# 1_Power.net
KiCad netlist of a schematic drawn in Altium Designer
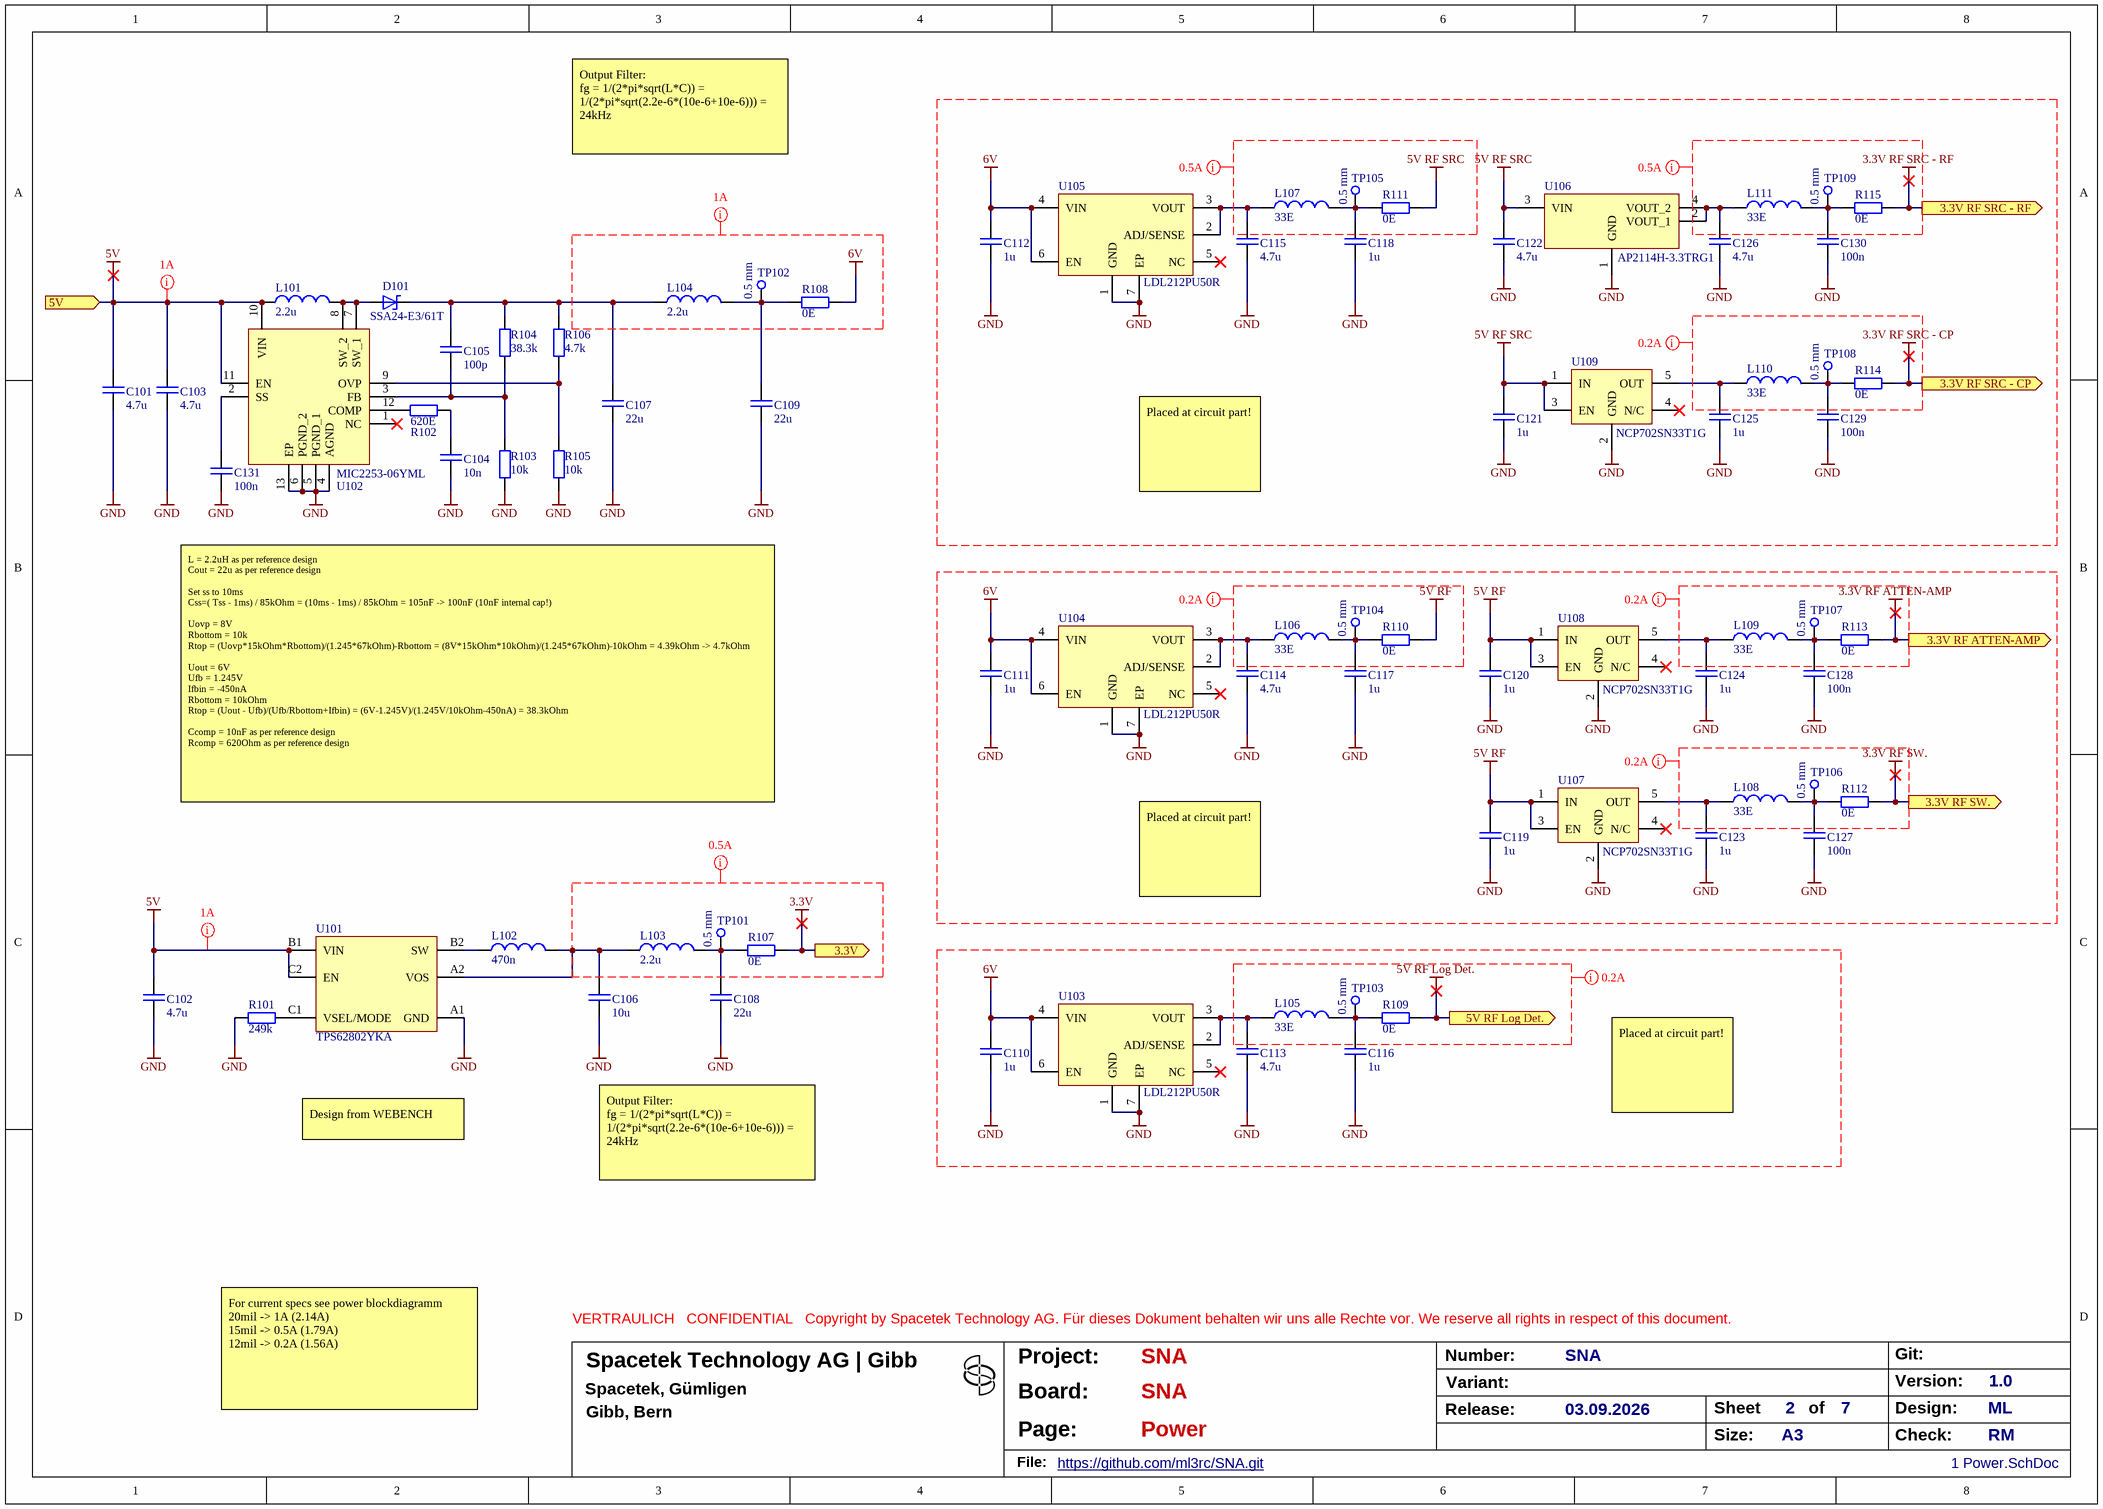
[diagram p0: 1 Power.SchDoc]

(export (version "E")
  (design (tool "Eeschema 10.0.6"))
  (components
    (comp (ref "C101")
      (value "4.7u")
      (footprint "STT--CC--0805")
      (description "Capacitor ceramic 4.7u 25V 10% X7R  SMD--0805")
      (fields (field (name "MANUFACTURER") "Samsung Electro-Mechanics") (field (name "TOLERANCE") "10%"))
      (libsource (lib "Spacetek Technology AG") (part "C--std"))
    )
    (comp (ref "C102")
      (value "4.7u")
      (footprint "STT--CC--0805")
      (description "Capacitor ceramic 4.7u 25V 10% X7R  SMD--0805")
      (fields (field (name "MANUFACTURER") "Samsung Electro-Mechanics") (field (name "TOLERANCE") "10%"))
      (libsource (lib "Spacetek Technology AG") (part "C--std"))
    )
    (comp (ref "C103")
      (value "4.7u")
      (footprint "STT--CC--0805")
      (description "Capacitor ceramic 4.7u 25V 10% X7R  SMD--0805")
      (fields (field (name "MANUFACTURER") "Samsung Electro-Mechanics") (field (name "TOLERANCE") "10%"))
      (libsource (lib "Spacetek Technology AG") (part "C--std"))
    )
    (comp (ref "C104")
      (value "10n")
      (footprint "STT--CC--0603")
      (description "Capacitor ceramic 10n 50V 5% C0G/NPO  SMD--0603")
      (fields (field (name "VOLTAGE") "50V") (field (name "TOLERANCE") "+/-5%"))
      (libsource (lib "Spacetek Technology AG") (part "C--std"))
    )
    (comp (ref "C105")
      (value "100p")
      (footprint "STT--CC--0402")
      (description "Capacitor ceramic 100p 50V 5% C0G AEC-Q200 SMD--0402")
      (fields
        (field (name "PARTNUMBER") "CL05C101JB51PND")
        (field (name "MANUFACTURER") "Samsung Electro-Mechanics")
      )
      (libsource (lib "Spacetek Technology AG") (part "C--std"))
    )
    (comp (ref "C106")
      (value "10u")
      (footprint "STT--CC--0603")
      (description "Capacitor ceramic 10u 25V 20% X5R  SMD--0603")
      (fields (field (name "TOLERANCE") "20%") (field (name "PARTNUMBER") "GRM188R61E106MA73D"))
      (libsource (lib "Spacetek Technology AG") (part "C--std"))
    )
    (comp (ref "C107")
      (value "22u")
      (footprint "STT--CC--0805")
      (description "Capacitor ceramic 22u 25V 20% X5R  SMD--0805")
      (fields (field (name "VOLTAGE") "25V") (field (name "TOLERANCE") "20%"))
      (libsource (lib "Spacetek Technology AG") (part "C--std"))
    )
    (comp (ref "C108")
      (value "22u")
      (footprint "STT--CC--0805")
      (description "Capacitor ceramic 22u 25V 20% X5R  SMD--0805")
      (fields (field (name "VOLTAGE") "25V") (field (name "TOLERANCE") "20%"))
      (libsource (lib "Spacetek Technology AG") (part "C--std"))
    )
    (comp (ref "C109")
      (value "22u")
      (footprint "STT--CC--0805")
      (description "Capacitor ceramic 22u 25V 20% X5R  SMD--0805")
      (fields (field (name "VOLTAGE") "25V") (field (name "TOLERANCE") "20%"))
      (libsource (lib "Spacetek Technology AG") (part "C--std"))
    )
    (comp (ref "C110")
      (value "1u")
      (footprint "STT--CC--0603")
      (description "CAP CER 1UF 35V X7R 0603 10%")
      (fields
        (field (name "MANUFACTURER") "TDK Corporation")
        (field (name "PARTNUMBER") "C1608X7R1V105K080AC")
      )
      (libsource (lib "Spacetek Technology AG") (part "C--std"))
    )
    (comp (ref "C111")
      (value "1u")
      (footprint "STT--CC--0603")
      (description "CAP CER 1UF 35V X7R 0603 10%")
      (fields
        (field (name "MANUFACTURER") "TDK Corporation")
        (field (name "PARTNUMBER") "C1608X7R1V105K080AC")
      )
      (libsource (lib "Spacetek Technology AG") (part "C--std"))
    )
    (comp (ref "C112")
      (value "1u")
      (footprint "STT--CC--0603")
      (description "CAP CER 1UF 35V X7R 0603 10%")
      (fields
        (field (name "MANUFACTURER") "TDK Corporation")
        (field (name "PARTNUMBER") "C1608X7R1V105K080AC")
      )
      (libsource (lib "Spacetek Technology AG") (part "C--std"))
    )
    (comp (ref "C113")
      (value "4.7u")
      (footprint "STT--CC--0805")
      (description "Capacitor ceramic 4.7u 25V 10% X7R  SMD--0805")
      (fields (field (name "MANUFACTURER") "Samsung Electro-Mechanics") (field (name "TOLERANCE") "10%"))
      (libsource (lib "Spacetek Technology AG") (part "C--std"))
    )
    (comp (ref "C114")
      (value "4.7u")
      (footprint "STT--CC--0805")
      (description "Capacitor ceramic 4.7u 25V 10% X7R  SMD--0805")
      (fields (field (name "MANUFACTURER") "Samsung Electro-Mechanics") (field (name "TOLERANCE") "10%"))
      (libsource (lib "Spacetek Technology AG") (part "C--std"))
    )
    (comp (ref "C115")
      (value "4.7u")
      (footprint "STT--CC--0805")
      (description "Capacitor ceramic 4.7u 25V 10% X7R  SMD--0805")
      (fields (field (name "MANUFACTURER") "Samsung Electro-Mechanics") (field (name "TOLERANCE") "10%"))
      (libsource (lib "Spacetek Technology AG") (part "C--std"))
    )
    (comp (ref "C116")
      (value "1u")
      (footprint "STT--CC--0603")
      (description "CAP CER 1UF 35V X7R 0603 10%")
      (fields
        (field (name "MANUFACTURER") "TDK Corporation")
        (field (name "PARTNUMBER") "C1608X7R1V105K080AC")
      )
      (libsource (lib "Spacetek Technology AG") (part "C--std"))
    )
    (comp (ref "C117")
      (value "1u")
      (footprint "STT--CC--0603")
      (description "CAP CER 1UF 35V X7R 0603 10%")
      (fields
        (field (name "MANUFACTURER") "TDK Corporation")
        (field (name "PARTNUMBER") "C1608X7R1V105K080AC")
      )
      (libsource (lib "Spacetek Technology AG") (part "C--std"))
    )
    (comp (ref "C118")
      (value "1u")
      (footprint "STT--CC--0603")
      (description "CAP CER 1UF 35V X7R 0603 10%")
      (fields
        (field (name "MANUFACTURER") "TDK Corporation")
        (field (name "PARTNUMBER") "C1608X7R1V105K080AC")
      )
      (libsource (lib "Spacetek Technology AG") (part "C--std"))
    )
    (comp (ref "C119")
      (value "1u")
      (footprint "STT--CC--0603")
      (description "CAP CER 1UF 35V X7R 0603 10%")
      (fields
        (field (name "MANUFACTURER") "TDK Corporation")
        (field (name "PARTNUMBER") "C1608X7R1V105K080AC")
      )
      (libsource (lib "Spacetek Technology AG") (part "C--std"))
    )
    (comp (ref "C120")
      (value "1u")
      (footprint "STT--CC--0603")
      (description "CAP CER 1UF 35V X7R 0603 10%")
      (fields
        (field (name "MANUFACTURER") "TDK Corporation")
        (field (name "PARTNUMBER") "C1608X7R1V105K080AC")
      )
      (libsource (lib "Spacetek Technology AG") (part "C--std"))
    )
    (comp (ref "C121")
      (value "1u")
      (footprint "STT--CC--0603")
      (description "CAP CER 1UF 35V X7R 0603 10%")
      (fields
        (field (name "MANUFACTURER") "TDK Corporation")
        (field (name "PARTNUMBER") "C1608X7R1V105K080AC")
      )
      (libsource (lib "Spacetek Technology AG") (part "C--std"))
    )
    (comp (ref "C122")
      (value "4.7u")
      (footprint "STT--CC--0805")
      (description "Capacitor ceramic 4.7u 25V 10% X7R  SMD--0805")
      (fields (field (name "MANUFACTURER") "Samsung Electro-Mechanics") (field (name "TOLERANCE") "10%"))
      (libsource (lib "Spacetek Technology AG") (part "C--std"))
    )
    (comp (ref "C123")
      (value "1u")
      (footprint "STT--CC--0603")
      (description "CAP CER 1UF 35V X7R 0603 10%")
      (fields
        (field (name "MANUFACTURER") "TDK Corporation")
        (field (name "PARTNUMBER") "C1608X7R1V105K080AC")
      )
      (libsource (lib "Spacetek Technology AG") (part "C--std"))
    )
    (comp (ref "C124")
      (value "1u")
      (footprint "STT--CC--0603")
      (description "CAP CER 1UF 35V X7R 0603 10%")
      (fields
        (field (name "MANUFACTURER") "TDK Corporation")
        (field (name "PARTNUMBER") "C1608X7R1V105K080AC")
      )
      (libsource (lib "Spacetek Technology AG") (part "C--std"))
    )
    (comp (ref "C125")
      (value "1u")
      (footprint "STT--CC--0603")
      (description "CAP CER 1UF 35V X7R 0603 10%")
      (fields
        (field (name "MANUFACTURER") "TDK Corporation")
        (field (name "PARTNUMBER") "C1608X7R1V105K080AC")
      )
      (libsource (lib "Spacetek Technology AG") (part "C--std"))
    )
    (comp (ref "C126")
      (value "4.7u")
      (footprint "STT--CC--0805")
      (description "Capacitor ceramic 4.7u 25V 10% X7R  SMD--0805")
      (fields (field (name "MANUFACTURER") "Samsung Electro-Mechanics") (field (name "TOLERANCE") "10%"))
      (libsource (lib "Spacetek Technology AG") (part "C--std"))
    )
    (comp (ref "C127")
      (value "100n")
      (footprint "STT--CC--0402")
      (description "Capacitor ceramic 100n 16V 10% X7R  SMD--0402")
      (fields (field (name "VOLTAGE") "16V") (field (name "TOLERANCE") "10%"))
      (libsource (lib "Spacetek Technology AG") (part "C--std"))
    )
    (comp (ref "C128")
      (value "100n")
      (footprint "STT--CC--0402")
      (description "Capacitor ceramic 100n 16V 10% X7R  SMD--0402")
      (fields (field (name "VOLTAGE") "16V") (field (name "TOLERANCE") "10%"))
      (libsource (lib "Spacetek Technology AG") (part "C--std"))
    )
    (comp (ref "C129")
      (value "100n")
      (footprint "STT--CC--0402")
      (description "Capacitor ceramic 100n 16V 10% X7R  SMD--0402")
      (fields (field (name "VOLTAGE") "16V") (field (name "TOLERANCE") "10%"))
      (libsource (lib "Spacetek Technology AG") (part "C--std"))
    )
    (comp (ref "C130")
      (value "100n")
      (footprint "STT--CC--0402")
      (description "Capacitor ceramic 100n 16V 10% X7R  SMD--0402")
      (fields (field (name "VOLTAGE") "16V") (field (name "TOLERANCE") "10%"))
      (libsource (lib "Spacetek Technology AG") (part "C--std"))
    )
    (comp (ref "C131")
      (value "100n")
      (footprint "STT--CC--0402")
      (description "Capacitor ceramic 100n 16V 10% X7R  SMD--0402")
      (fields (field (name "VOLTAGE") "16V") (field (name "TOLERANCE") "10%"))
      (libsource (lib "Spacetek Technology AG") (part "C--std"))
    )
    (comp (ref "D101")
      (value "SSA24-E3/61T")
      (footprint "STT--SD--SMA-DO-214AC")
      (description "Schottky Diode SSA24-E3/61T 40V 2A")
      (fields (field (name "MANUFACTURER") "Vishay") (field (name "VOLTAGE") "40V"))
      (libsource (lib "Spacetek Technology AG") (part "D--schottky"))
    )
    (comp (ref "L101")
      (value "2.2u")
      (footprint "BOU--LF--SRP4020FA")
      (description "Inductor SRP4020FA-2R2M 2.2u 3.1A 21.35mR 38MHz SMD--SRP4020FA")
      (fields (field (name "MANUFACTURER") "Bourns") (field (name "PARTNUMBER") "SRP4020FA-2R2M"))
      (libsource (lib "Spacetek Technology AG") (part "L--std"))
    )
    (comp (ref "L102")
      (value "470n")
      (footprint "MUR--FB--DFE252012F")
      (description "Inductor DFE252012F-R47M=P2 470n 7.4A 17mR  SMD--2520")
      (fields
        (field (name "PARTNUMBER") "DFE252012F-R47M=P2")
        (field (name "MANUFACTURER") "Murata Electronics")
      )
      (libsource (lib "Spacetek Technology AG") (part "L--std"))
    )
    (comp (ref "L103")
      (value "2.2u")
      (footprint "BOU--LF--SRP4020FA")
      (description "Inductor SRP4020FA-2R2M 2.2u 3.1A 21.35mR 38MHz SMD--SRP4020FA")
      (fields (field (name "MANUFACTURER") "Bourns") (field (name "PARTNUMBER") "SRP4020FA-2R2M"))
      (libsource (lib "Spacetek Technology AG") (part "L--std"))
    )
    (comp (ref "L104")
      (value "2.2u")
      (footprint "BOU--LF--SRP4020FA")
      (description "Inductor SRP4020FA-2R2M 2.2u 3.1A 21.35mR 38MHz SMD--SRP4020FA")
      (fields (field (name "MANUFACTURER") "Bourns") (field (name "PARTNUMBER") "SRP4020FA-2R2M"))
      (libsource (lib "Spacetek Technology AG") (part "L--std"))
    )
    (comp (ref "L105")
      (value "33E")
      (footprint "STT--FB--0402")
      (description "Ferrit Bead MPZ1005S330HT000 33E 3A 22mE SMD--0402")
      (fields (field (name "MANUFACTURER") "TDK Group") (field (name "PARTNUMBER") "MPZ1005S330HT000"))
      (libsource (lib "Spacetek Technology AG") (part "L--std"))
    )
    (comp (ref "L106")
      (value "33E")
      (footprint "STT--FB--0402")
      (description "Ferrit Bead MPZ1005S330HT000 33E 3A 22mE SMD--0402")
      (fields (field (name "MANUFACTURER") "TDK Group") (field (name "PARTNUMBER") "MPZ1005S330HT000"))
      (libsource (lib "Spacetek Technology AG") (part "L--std"))
    )
    (comp (ref "L107")
      (value "33E")
      (footprint "STT--FB--0402")
      (description "Ferrit Bead MPZ1005S330HT000 33E 3A 22mE SMD--0402")
      (fields (field (name "MANUFACTURER") "TDK Group") (field (name "PARTNUMBER") "MPZ1005S330HT000"))
      (libsource (lib "Spacetek Technology AG") (part "L--std"))
    )
    (comp (ref "L108")
      (value "33E")
      (footprint "STT--FB--0402")
      (description "Ferrit Bead MPZ1005S330HT000 33E 3A 22mE SMD--0402")
      (fields (field (name "MANUFACTURER") "TDK Group") (field (name "PARTNUMBER") "MPZ1005S330HT000"))
      (libsource (lib "Spacetek Technology AG") (part "L--std"))
    )
    (comp (ref "L109")
      (value "33E")
      (footprint "STT--FB--0402")
      (description "Ferrit Bead MPZ1005S330HT000 33E 3A 22mE SMD--0402")
      (fields (field (name "MANUFACTURER") "TDK Group") (field (name "PARTNUMBER") "MPZ1005S330HT000"))
      (libsource (lib "Spacetek Technology AG") (part "L--std"))
    )
    (comp (ref "L110")
      (value "33E")
      (footprint "STT--FB--0402")
      (description "Ferrit Bead MPZ1005S330HT000 33E 3A 22mE SMD--0402")
      (fields (field (name "MANUFACTURER") "TDK Group") (field (name "PARTNUMBER") "MPZ1005S330HT000"))
      (libsource (lib "Spacetek Technology AG") (part "L--std"))
    )
    (comp (ref "L111")
      (value "33E")
      (footprint "STT--FB--0402")
      (description "Ferrit Bead MPZ1005S330HT000 33E 3A 22mE SMD--0402")
      (fields (field (name "MANUFACTURER") "TDK Group") (field (name "PARTNUMBER") "MPZ1005S330HT000"))
      (libsource (lib "Spacetek Technology AG") (part "L--std"))
    )
    (comp (ref "R101")
      (value "249k")
      (footprint "STT--RC--0603")
      (description "Resistor 249k 75V 0.1W 0.1% SMD--0603")
      (fields (field (name "TOLERANCE") "0.1%") (field (name "MANUFACTURER") "YAGEO"))
      (libsource (lib "Spacetek Technology AG") (part "R--std"))
    )
    (comp (ref "R102")
      (value "620E")
      (footprint "STT--RC--0603")
      (description "Resistor 620E 75V  0.1W 0.1% ±25ppm/°C SMD--0603")
      (fields (field (name "TOLERANCE") "1%") (field (name "MANUFACTURER") "Yageo"))
      (libsource (lib "Spacetek Technology AG") (part "R--std"))
    )
    (comp (ref "R103")
      (value "10k")
      (footprint "STT--RC--0603")
      (description "Resistor 10k 75V  0.1W 0.1% 25ppm SMD--0603")
      (fields (field (name "POWER") "0.1W") (field (name "MANUFACTURER") "Susumu"))
      (libsource (lib "") (part "R--std_2"))
    )
    (comp (ref "R104")
      (value "38.3k")
      (footprint "STT--RC--0603")
      (description "Resistor 38.3k 75V  0.1W 0.1%  SMD--0603")
      (fields (field (name "PARTNUMBER") "RT0603BRD0738K3L") (field (name "VOLTAGE") "75V"))
      (libsource (lib "") (part "R--std_2"))
    )
    (comp (ref "R105")
      (value "10k")
      (footprint "STT--RC--0603")
      (description "Resistor 10k 75V  0.1W 0.1% 25ppm SMD--0603")
      (fields (field (name "POWER") "0.1W") (field (name "MANUFACTURER") "Susumu"))
      (libsource (lib "") (part "R--std_2"))
    )
    (comp (ref "R106")
      (value "4.7k")
      (footprint "STT--RC--0603")
      (description "Resistor 4.7k 75V  0.1W 1%  SMD--0603")
      (fields (field (name "TOLERANCE") "1%") (field (name "VOLTAGE") "75V"))
      (libsource (lib "") (part "R--std_2"))
    )
    (comp (ref "R107")
      (value "0E")
      (footprint "STT--RC--0603")
      (description "Resistor 0E 75V  0.125W   SMD--0603")
      (fields (field (name "MANUFACTURER") "Vishay") (field (name "POWER") "0.125W"))
      (libsource (lib "") (part "R--std_1"))
    )
    (comp (ref "R108")
      (value "0E")
      (footprint "STT--RC--0603")
      (description "Resistor 0E 75V  0.125W   SMD--0603")
      (fields (field (name "MANUFACTURER") "Vishay") (field (name "POWER") "0.125W"))
      (libsource (lib "") (part "R--std_1"))
    )
    (comp (ref "R109")
      (value "0E")
      (footprint "STT--RC--0603")
      (description "Resistor 0E 75V  0.125W   SMD--0603")
      (fields (field (name "MANUFACTURER") "Vishay") (field (name "POWER") "0.125W"))
      (libsource (lib "") (part "R--std_1"))
    )
    (comp (ref "R110")
      (value "0E")
      (footprint "STT--RC--0603")
      (description "Resistor 0E 75V  0.125W   SMD--0603")
      (fields (field (name "MANUFACTURER") "Vishay") (field (name "POWER") "0.125W"))
      (libsource (lib "") (part "R--std_1"))
    )
    (comp (ref "R111")
      (value "0E")
      (footprint "STT--RC--0603")
      (description "Resistor 0E 75V  0.125W   SMD--0603")
      (fields (field (name "MANUFACTURER") "Vishay") (field (name "POWER") "0.125W"))
      (libsource (lib "") (part "R--std_1"))
    )
    (comp (ref "R112")
      (value "0E")
      (footprint "STT--RC--0603")
      (description "Resistor 0E 75V  0.125W   SMD--0603")
      (fields (field (name "MANUFACTURER") "Vishay") (field (name "POWER") "0.125W"))
      (libsource (lib "") (part "R--std_1"))
    )
    (comp (ref "R113")
      (value "0E")
      (footprint "STT--RC--0603")
      (description "Resistor 0E 75V  0.125W   SMD--0603")
      (fields (field (name "MANUFACTURER") "Vishay") (field (name "POWER") "0.125W"))
      (libsource (lib "") (part "R--std_1"))
    )
    (comp (ref "R114")
      (value "0E")
      (footprint "STT--RC--0603")
      (description "Resistor 0E 75V  0.125W   SMD--0603")
      (fields (field (name "MANUFACTURER") "Vishay") (field (name "POWER") "0.125W"))
      (libsource (lib "") (part "R--std_1"))
    )
    (comp (ref "R115")
      (value "0E")
      (footprint "STT--RC--0603")
      (description "Resistor 0E 75V  0.125W   SMD--0603")
      (fields (field (name "MANUFACTURER") "Vishay") (field (name "POWER") "0.125W"))
      (libsource (lib "") (part "R--std_1"))
    )
    (comp (ref "TP101")
      (value "0.5 mm")
      (footprint "STT--DO--TP-0.5")
      (description "Pad TP SMD--Pad 0.5")
      (fields (field (name "PARTNUMBER") "TP"))
      (libsource (lib "Spacetek Technology AG") (part "TP--Testpoint"))
    )
    (comp (ref "TP102")
      (value "0.5 mm")
      (footprint "STT--DO--TP-0.5")
      (description "Pad TP SMD--Pad 0.5")
      (fields (field (name "PARTNUMBER") "TP"))
      (libsource (lib "Spacetek Technology AG") (part "TP--Testpoint"))
    )
    (comp (ref "TP103")
      (value "0.5 mm")
      (footprint "STT--DO--TP-0.5")
      (description "Pad TP SMD--Pad 0.5")
      (fields (field (name "PARTNUMBER") "TP"))
      (libsource (lib "Spacetek Technology AG") (part "TP--Testpoint"))
    )
    (comp (ref "TP104")
      (value "0.5 mm")
      (footprint "STT--DO--TP-0.5")
      (description "Pad TP SMD--Pad 0.5")
      (fields (field (name "PARTNUMBER") "TP"))
      (libsource (lib "Spacetek Technology AG") (part "TP--Testpoint"))
    )
    (comp (ref "TP105")
      (value "0.5 mm")
      (footprint "STT--DO--TP-0.5")
      (description "Pad TP SMD--Pad 0.5")
      (fields (field (name "PARTNUMBER") "TP"))
      (libsource (lib "Spacetek Technology AG") (part "TP--Testpoint"))
    )
    (comp (ref "TP106")
      (value "0.5 mm")
      (footprint "STT--DO--TP-0.5")
      (description "Pad TP SMD--Pad 0.5")
      (fields (field (name "PARTNUMBER") "TP"))
      (libsource (lib "Spacetek Technology AG") (part "TP--Testpoint"))
    )
    (comp (ref "TP107")
      (value "0.5 mm")
      (footprint "STT--DO--TP-0.5")
      (description "Pad TP SMD--Pad 0.5")
      (fields (field (name "PARTNUMBER") "TP"))
      (libsource (lib "Spacetek Technology AG") (part "TP--Testpoint"))
    )
    (comp (ref "TP108")
      (value "0.5 mm")
      (footprint "STT--DO--TP-0.5")
      (description "Pad TP SMD--Pad 0.5")
      (fields (field (name "PARTNUMBER") "TP"))
      (libsource (lib "Spacetek Technology AG") (part "TP--Testpoint"))
    )
    (comp (ref "TP109")
      (value "0.5 mm")
      (footprint "STT--DO--TP-0.5")
      (description "Pad TP SMD--Pad 0.5")
      (fields (field (name "PARTNUMBER") "TP"))
      (libsource (lib "Spacetek Technology AG") (part "TP--Testpoint"))
    )
    (comp (ref "U101")
      (value "TPS62802YKA")
      (footprint "TEI--IC--BGA6")
      (description "DCDC Buck Converter 1.75-V to 5.5-V input 1-A ultra-low IQ")
      (fields (field (name "MANUFACTURER") "Texas Instruments"))
      (libsource (lib "Spacetek Technology AG") (part "U--TPS62802YKA"))
    )
    (comp (ref "U102")
      (value "MIC2253-06YML")
      (footprint "MC--IC--SON50P300X300X90-13N-D")
      (description "Switching Voltage Regulators 3.5A 1MHz High Efficiency Boost Regulator with OVP & Softstart")
      (fields (field (name "MANUFACTURER") "Microchip"))
      (libsource (lib "Spacetek Technology AG") (part "U--MIC2253"))
    )
    (comp (ref "U103")
      (value "LDL212PU50R")
      (footprint "STM--IC--DFN-6")
      (description "LDO 1.2A Low Drop Linear Regulator IC")
      (fields (field (name "MANUFACTURER") "STMicroelectronics"))
      (libsource (lib "Spacetek Technology AG") (part "U--LDL212PU"))
    )
    (comp (ref "U104")
      (value "LDL212PU50R")
      (footprint "STM--IC--DFN-6")
      (description "LDO 1.2A Low Drop Linear Regulator IC")
      (fields (field (name "MANUFACTURER") "STMicroelectronics"))
      (libsource (lib "Spacetek Technology AG") (part "U--LDL212PU"))
    )
    (comp (ref "U105")
      (value "LDL212PU50R")
      (footprint "STM--IC--DFN-6")
      (description "LDO 1.2A Low Drop Linear Regulator IC")
      (fields (field (name "MANUFACTURER") "STMicroelectronics"))
      (libsource (lib "Spacetek Technology AG") (part "U--LDL212PU"))
    )
    (comp (ref "U106")
      (value "AP2114H-3.3TRG1")
      (footprint "DI--IC--SOT-223-3")
      (description "LDO 3.3V Fixed 1A Low Noise CMOS LDO Regulator With Enable")
      (fields (field (name "MANUFACTURER") "Diodes Incoporated"))
      (libsource (lib "Spacetek Technology AG") (part "U--AP2114H"))
    )
    (comp (ref "U107")
      (value "NCP702SN33T1G")
      (footprint "ON--IC--SOT-23-5")
      (description "LDO 3.3V Fixed 200 mA")
      (fields (field (name "MANUFACTURER") "onsemi"))
      (libsource (lib "Spacetek Technology AG") (part "U--NCP702SN"))
    )
    (comp (ref "U108")
      (value "NCP702SN33T1G")
      (footprint "ON--IC--SOT-23-5")
      (description "LDO 3.3V Fixed 200 mA")
      (fields (field (name "MANUFACTURER") "onsemi"))
      (libsource (lib "Spacetek Technology AG") (part "U--NCP702SN"))
    )
    (comp (ref "U109")
      (value "NCP702SN33T1G")
      (footprint "ON--IC--SOT-23-5")
      (description "LDO 3.3V Fixed 200 mA")
      (fields (field (name "MANUFACTURER") "onsemi"))
      (libsource (lib "Spacetek Technology AG") (part "U--NCP702SN"))
    )
  )
  (nets
    (net (code "1") (name "3.3V") (class "Default")
      (node (ref "R107") (pin "2") (pinfunction "2_2") (pintype "passive"))
    )
    (net (code "2") (name "3.3V RF ATTEN-AMP") (class "Default")
      (node (ref "R113") (pin "2") (pinfunction "2_2") (pintype "passive"))
    )
    (net (code "3") (name "3.3V RF SRC - CP") (class "Default")
      (node (ref "R114") (pin "2") (pinfunction "2_2") (pintype "passive"))
    )
    (net (code "4") (name "3.3V RF SRC - RF") (class "Default")
      (node (ref "R115") (pin "2") (pinfunction "2_2") (pintype "passive"))
    )
    (net (code "5") (name "3.3V RF SW.") (class "Default")
      (node (ref "R112") (pin "2") (pinfunction "2_2") (pintype "passive"))
    )
    (net (code "6") (name "5V") (class "Default")
      (node (ref "C101") (pin "2") (pinfunction "2_2") (pintype "passive"))
      (node (ref "C102") (pin "2") (pinfunction "2_2") (pintype "passive"))
      (node (ref "C103") (pin "2") (pinfunction "2_2") (pintype "passive"))
      (node (ref "L101") (pin "1") (pinfunction "1_1") (pintype "passive"))
      (node (ref "U101") (pin "B1") (pinfunction "VIN_B1") (pintype "passive"))
      (node (ref "U101") (pin "C2") (pinfunction "EN_C2") (pintype "passive"))
      (node (ref "U102") (pin "10") (pinfunction "VIN_10") (pintype "passive"))
      (node (ref "U102") (pin "11") (pinfunction "EN_11") (pintype "passive"))
    )
    (net (code "7") (name "5V RF") (class "Default")
      (node (ref "C119") (pin "2") (pinfunction "2_2") (pintype "passive"))
      (node (ref "C120") (pin "2") (pinfunction "2_2") (pintype "passive"))
      (node (ref "R110") (pin "2") (pinfunction "2_2") (pintype "passive"))
      (node (ref "U107") (pin "1") (pinfunction "IN_1") (pintype "passive"))
      (node (ref "U107") (pin "3") (pinfunction "EN_3") (pintype "passive"))
      (node (ref "U108") (pin "1") (pinfunction "IN_1") (pintype "passive"))
      (node (ref "U108") (pin "3") (pinfunction "EN_3") (pintype "passive"))
    )
    (net (code "8") (name "5V RF Log Det.") (class "Default")
      (node (ref "R109") (pin "2") (pinfunction "2_2") (pintype "passive"))
    )
    (net (code "9") (name "5V RF SRC") (class "Default")
      (node (ref "C121") (pin "2") (pinfunction "2_2") (pintype "passive"))
      (node (ref "C122") (pin "2") (pinfunction "2_2") (pintype "passive"))
      (node (ref "R111") (pin "2") (pinfunction "2_2") (pintype "passive"))
      (node (ref "U106") (pin "3") (pinfunction "VIN_3") (pintype "passive"))
      (node (ref "U109") (pin "1") (pinfunction "IN_1") (pintype "passive"))
      (node (ref "U109") (pin "3") (pinfunction "EN_3") (pintype "passive"))
    )
    (net (code "10") (name "6V") (class "Default")
      (node (ref "C110") (pin "2") (pinfunction "2_2") (pintype "passive"))
      (node (ref "C111") (pin "2") (pinfunction "2_2") (pintype "passive"))
      (node (ref "C112") (pin "2") (pinfunction "2_2") (pintype "passive"))
      (node (ref "R108") (pin "2") (pinfunction "2_2") (pintype "passive"))
      (node (ref "U103") (pin "4") (pinfunction "VIN_4") (pintype "passive"))
      (node (ref "U103") (pin "6") (pinfunction "EN_6") (pintype "passive"))
      (node (ref "U104") (pin "4") (pinfunction "VIN_4") (pintype "passive"))
      (node (ref "U104") (pin "6") (pinfunction "EN_6") (pintype "passive"))
      (node (ref "U105") (pin "4") (pinfunction "VIN_4") (pintype "passive"))
      (node (ref "U105") (pin "6") (pinfunction "EN_6") (pintype "passive"))
    )
    (net (code "11") (name "GND") (class "Default")
      (node (ref "C101") (pin "1") (pinfunction "1_1") (pintype "passive"))
      (node (ref "C102") (pin "1") (pinfunction "1_1") (pintype "passive"))
      (node (ref "C103") (pin "1") (pinfunction "1_1") (pintype "passive"))
      (node (ref "C104") (pin "1") (pinfunction "1_1") (pintype "passive"))
      (node (ref "C106") (pin "1") (pinfunction "1_1") (pintype "passive"))
      (node (ref "C107") (pin "1") (pinfunction "1_1") (pintype "passive"))
      (node (ref "C108") (pin "1") (pinfunction "1_1") (pintype "passive"))
      (node (ref "C109") (pin "1") (pinfunction "1_1") (pintype "passive"))
      (node (ref "C110") (pin "1") (pinfunction "1_1") (pintype "passive"))
      (node (ref "C111") (pin "1") (pinfunction "1_1") (pintype "passive"))
      (node (ref "C112") (pin "1") (pinfunction "1_1") (pintype "passive"))
      (node (ref "C113") (pin "1") (pinfunction "1_1") (pintype "passive"))
      (node (ref "C114") (pin "1") (pinfunction "1_1") (pintype "passive"))
      (node (ref "C115") (pin "1") (pinfunction "1_1") (pintype "passive"))
      (node (ref "C116") (pin "1") (pinfunction "1_1") (pintype "passive"))
      (node (ref "C117") (pin "1") (pinfunction "1_1") (pintype "passive"))
      (node (ref "C118") (pin "1") (pinfunction "1_1") (pintype "passive"))
      (node (ref "C119") (pin "1") (pinfunction "1_1") (pintype "passive"))
      (node (ref "C120") (pin "1") (pinfunction "1_1") (pintype "passive"))
      (node (ref "C121") (pin "1") (pinfunction "1_1") (pintype "passive"))
      (node (ref "C122") (pin "1") (pinfunction "1_1") (pintype "passive"))
      (node (ref "C123") (pin "1") (pinfunction "1_1") (pintype "passive"))
      (node (ref "C124") (pin "1") (pinfunction "1_1") (pintype "passive"))
      (node (ref "C125") (pin "1") (pinfunction "1_1") (pintype "passive"))
      (node (ref "C126") (pin "1") (pinfunction "1_1") (pintype "passive"))
      (node (ref "C127") (pin "1") (pinfunction "1_1") (pintype "passive"))
      (node (ref "C128") (pin "1") (pinfunction "1_1") (pintype "passive"))
      (node (ref "C129") (pin "1") (pinfunction "1_1") (pintype "passive"))
      (node (ref "C130") (pin "1") (pinfunction "1_1") (pintype "passive"))
      (node (ref "C131") (pin "1") (pinfunction "1_1") (pintype "passive"))
      (node (ref "R101") (pin "2") (pinfunction "2_2") (pintype "passive"))
      (node (ref "R103") (pin "1") (pinfunction "1_1") (pintype "passive"))
      (node (ref "R105") (pin "1") (pinfunction "1_1") (pintype "passive"))
      (node (ref "U101") (pin "A1") (pinfunction "GND_A1") (pintype "passive"))
      (node (ref "U102") (pin "13") (pinfunction "EP_13") (pintype "passive"))
      (node (ref "U102") (pin "4") (pinfunction "AGND_4") (pintype "passive"))
      (node (ref "U102") (pin "5") (pinfunction "PGND_1_5") (pintype "passive"))
      (node (ref "U102") (pin "6") (pinfunction "PGND_2_6") (pintype "passive"))
      (node (ref "U103") (pin "1") (pinfunction "GND_1") (pintype "passive"))
      (node (ref "U103") (pin "7") (pinfunction "EP_7") (pintype "passive"))
      (node (ref "U104") (pin "1") (pinfunction "GND_1") (pintype "passive"))
      (node (ref "U104") (pin "7") (pinfunction "EP_7") (pintype "passive"))
      (node (ref "U105") (pin "1") (pinfunction "GND_1") (pintype "passive"))
      (node (ref "U105") (pin "7") (pinfunction "EP_7") (pintype "passive"))
      (node (ref "U106") (pin "1") (pinfunction "GND_1") (pintype "passive"))
      (node (ref "U107") (pin "2") (pinfunction "GND_2") (pintype "passive"))
      (node (ref "U108") (pin "2") (pinfunction "GND_2") (pintype "passive"))
      (node (ref "U109") (pin "2") (pinfunction "GND_2") (pintype "passive"))
    )
    (net (code "12") (name "Net-(C104-Pad2)") (class "Default")
      (node (ref "C104") (pin "2") (pinfunction "2_2") (pintype "passive"))
      (node (ref "R102") (pin "1") (pinfunction "1_1") (pintype "passive"))
    )
    (net (code "13") (name "Net-(C108-Pad2)") (class "Default")
      (node (ref "C108") (pin "2") (pinfunction "2_2") (pintype "passive"))
      (node (ref "L103") (pin "2") (pinfunction "2_2") (pintype "passive"))
      (node (ref "R107") (pin "1") (pinfunction "1_1") (pintype "passive"))
      (node (ref "TP101") (pin "1") (pinfunction "1_1") (pintype "passive"))
    )
    (net (code "14") (name "Net-(C109-Pad2)") (class "Default")
      (node (ref "C109") (pin "2") (pinfunction "2_2") (pintype "passive"))
      (node (ref "L104") (pin "2") (pinfunction "2_2") (pintype "passive"))
      (node (ref "R108") (pin "1") (pinfunction "1_1") (pintype "passive"))
      (node (ref "TP102") (pin "1") (pinfunction "1_1") (pintype "passive"))
    )
    (net (code "15") (name "Net-(C116-Pad2)") (class "Default")
      (node (ref "C116") (pin "2") (pinfunction "2_2") (pintype "passive"))
      (node (ref "L105") (pin "2") (pinfunction "2_2") (pintype "passive"))
      (node (ref "R109") (pin "1") (pinfunction "1_1") (pintype "passive"))
      (node (ref "TP103") (pin "1") (pinfunction "1_1") (pintype "passive"))
    )
    (net (code "16") (name "Net-(C117-Pad2)") (class "Default")
      (node (ref "C117") (pin "2") (pinfunction "2_2") (pintype "passive"))
      (node (ref "L106") (pin "2") (pinfunction "2_2") (pintype "passive"))
      (node (ref "R110") (pin "1") (pinfunction "1_1") (pintype "passive"))
      (node (ref "TP104") (pin "1") (pinfunction "1_1") (pintype "passive"))
    )
    (net (code "17") (name "Net-(C118-Pad2)") (class "Default")
      (node (ref "C118") (pin "2") (pinfunction "2_2") (pintype "passive"))
      (node (ref "L107") (pin "2") (pinfunction "2_2") (pintype "passive"))
      (node (ref "R111") (pin "1") (pinfunction "1_1") (pintype "passive"))
      (node (ref "TP105") (pin "1") (pinfunction "1_1") (pintype "passive"))
    )
    (net (code "18") (name "Net-(C127-Pad2)") (class "Default")
      (node (ref "C127") (pin "2") (pinfunction "2_2") (pintype "passive"))
      (node (ref "L108") (pin "2") (pinfunction "2_2") (pintype "passive"))
      (node (ref "R112") (pin "1") (pinfunction "1_1") (pintype "passive"))
      (node (ref "TP106") (pin "1") (pinfunction "1_1") (pintype "passive"))
    )
    (net (code "19") (name "Net-(C128-Pad2)") (class "Default")
      (node (ref "C128") (pin "2") (pinfunction "2_2") (pintype "passive"))
      (node (ref "L109") (pin "2") (pinfunction "2_2") (pintype "passive"))
      (node (ref "R113") (pin "1") (pinfunction "1_1") (pintype "passive"))
      (node (ref "TP107") (pin "1") (pinfunction "1_1") (pintype "passive"))
    )
    (net (code "20") (name "Net-(C129-Pad2)") (class "Default")
      (node (ref "C129") (pin "2") (pinfunction "2_2") (pintype "passive"))
      (node (ref "L110") (pin "2") (pinfunction "2_2") (pintype "passive"))
      (node (ref "R114") (pin "1") (pinfunction "1_1") (pintype "passive"))
      (node (ref "TP108") (pin "1") (pinfunction "1_1") (pintype "passive"))
    )
    (net (code "21") (name "Net-(C130-Pad2)") (class "Default")
      (node (ref "C130") (pin "2") (pinfunction "2_2") (pintype "passive"))
      (node (ref "L111") (pin "2") (pinfunction "2_2") (pintype "passive"))
      (node (ref "R115") (pin "1") (pinfunction "1_1") (pintype "passive"))
      (node (ref "TP109") (pin "1") (pinfunction "1_1") (pintype "passive"))
    )
    (net (code "22") (name "Net-(D101-A)") (class "Default")
      (node (ref "D101") (pin "1") (pinfunction "A_1") (pintype "passive"))
      (node (ref "L101") (pin "2") (pinfunction "2_2") (pintype "passive"))
      (node (ref "U102") (pin "7") (pinfunction "SW_1_7") (pintype "passive"))
      (node (ref "U102") (pin "8") (pinfunction "SW_2_8") (pintype "passive"))
    )
    (net (code "23") (name "Net-(D101-K)") (class "Default")
      (node (ref "C105") (pin "2") (pinfunction "2_2") (pintype "passive"))
      (node (ref "C107") (pin "2") (pinfunction "2_2") (pintype "passive"))
      (node (ref "D101") (pin "2") (pinfunction "K_2") (pintype "passive"))
      (node (ref "L104") (pin "1") (pinfunction "1_1") (pintype "passive"))
      (node (ref "R104") (pin "2") (pinfunction "2_2") (pintype "passive"))
      (node (ref "R106") (pin "2") (pinfunction "2_2") (pintype "passive"))
    )
    (net (code "24") (name "Net-(U101-SW)") (class "Default")
      (node (ref "L102") (pin "1") (pinfunction "1_1") (pintype "passive"))
      (node (ref "U101") (pin "B2") (pinfunction "SW_B2") (pintype "passive"))
    )
    (net (code "25") (name "Net-(U101-VOS)") (class "Default")
      (node (ref "C106") (pin "2") (pinfunction "2_2") (pintype "passive"))
      (node (ref "L102") (pin "2") (pinfunction "2_2") (pintype "passive"))
      (node (ref "L103") (pin "1") (pinfunction "1_1") (pintype "passive"))
      (node (ref "U101") (pin "A2") (pinfunction "VOS_A2") (pintype "passive"))
    )
    (net (code "26") (name "Net-(U101-VSEL{slash}MODE)") (class "Default")
      (node (ref "R101") (pin "1") (pinfunction "1_1") (pintype "passive"))
      (node (ref "U101") (pin "C1") (pinfunction "VSEL/MODE_C1") (pintype "passive"))
    )
    (net (code "27") (name "Net-(U102-COMP)") (class "Default")
      (node (ref "R102") (pin "2") (pinfunction "2_2") (pintype "passive"))
      (node (ref "U102") (pin "12") (pinfunction "COMP_12") (pintype "passive"))
    )
    (net (code "28") (name "Net-(U102-FB)") (class "Default")
      (node (ref "C105") (pin "1") (pinfunction "1_1") (pintype "passive"))
      (node (ref "R103") (pin "2") (pinfunction "2_2") (pintype "passive"))
      (node (ref "R104") (pin "1") (pinfunction "1_1") (pintype "passive"))
      (node (ref "U102") (pin "3") (pinfunction "FB_3") (pintype "passive"))
    )
    (net (code "29") (name "Net-(U102-OVP)") (class "Default")
      (node (ref "R105") (pin "2") (pinfunction "2_2") (pintype "passive"))
      (node (ref "R106") (pin "1") (pinfunction "1_1") (pintype "passive"))
      (node (ref "U102") (pin "9") (pinfunction "OVP_9") (pintype "passive"))
    )
    (net (code "30") (name "Net-(U102-SS)") (class "Default")
      (node (ref "C131") (pin "2") (pinfunction "2_2") (pintype "passive"))
      (node (ref "U102") (pin "2") (pinfunction "SS_2") (pintype "passive"))
    )
    (net (code "31") (name "Net-(U103-ADJ{slash}SENSE)") (class "Default")
      (node (ref "C113") (pin "2") (pinfunction "2_2") (pintype "passive"))
      (node (ref "L105") (pin "1") (pinfunction "1_1") (pintype "passive"))
      (node (ref "U103") (pin "2") (pinfunction "ADJ/SENSE_2") (pintype "passive"))
      (node (ref "U103") (pin "3") (pinfunction "VOUT_3") (pintype "passive"))
    )
    (net (code "32") (name "Net-(U104-ADJ{slash}SENSE)") (class "Default")
      (node (ref "C114") (pin "2") (pinfunction "2_2") (pintype "passive"))
      (node (ref "L106") (pin "1") (pinfunction "1_1") (pintype "passive"))
      (node (ref "U104") (pin "2") (pinfunction "ADJ/SENSE_2") (pintype "passive"))
      (node (ref "U104") (pin "3") (pinfunction "VOUT_3") (pintype "passive"))
    )
    (net (code "33") (name "Net-(U105-ADJ{slash}SENSE)") (class "Default")
      (node (ref "C115") (pin "2") (pinfunction "2_2") (pintype "passive"))
      (node (ref "L107") (pin "1") (pinfunction "1_1") (pintype "passive"))
      (node (ref "U105") (pin "2") (pinfunction "ADJ/SENSE_2") (pintype "passive"))
      (node (ref "U105") (pin "3") (pinfunction "VOUT_3") (pintype "passive"))
    )
    (net (code "34") (name "Net-(U106-VOUT_1)") (class "Default")
      (node (ref "C126") (pin "2") (pinfunction "2_2") (pintype "passive"))
      (node (ref "L111") (pin "1") (pinfunction "1_1") (pintype "passive"))
      (node (ref "U106") (pin "2") (pinfunction "VOUT_1_2") (pintype "passive"))
      (node (ref "U106") (pin "4") (pinfunction "VOUT_2_4") (pintype "passive"))
    )
    (net (code "35") (name "Net-(U107-OUT)") (class "Default")
      (node (ref "C123") (pin "2") (pinfunction "2_2") (pintype "passive"))
      (node (ref "L108") (pin "1") (pinfunction "1_1") (pintype "passive"))
      (node (ref "U107") (pin "5") (pinfunction "OUT_5") (pintype "passive"))
    )
    (net (code "36") (name "Net-(U108-OUT)") (class "Default")
      (node (ref "C124") (pin "2") (pinfunction "2_2") (pintype "passive"))
      (node (ref "L109") (pin "1") (pinfunction "1_1") (pintype "passive"))
      (node (ref "U108") (pin "5") (pinfunction "OUT_5") (pintype "passive"))
    )
    (net (code "37") (name "Net-(U109-OUT)") (class "Default")
      (node (ref "C125") (pin "2") (pinfunction "2_2") (pintype "passive"))
      (node (ref "L110") (pin "1") (pinfunction "1_1") (pintype "passive"))
      (node (ref "U109") (pin "5") (pinfunction "OUT_5") (pintype "passive"))
    )
    (net (code "38") (name "unconnected-(U102-NC-Pad1)") (class "Default")
      (node (ref "U102") (pin "1") (pinfunction "NC_1") (pintype "passive+no_connect"))
    )
    (net (code "39") (name "unconnected-(U103-NC-Pad5)") (class "Default")
      (node (ref "U103") (pin "5") (pinfunction "NC_5") (pintype "passive+no_connect"))
    )
    (net (code "40") (name "unconnected-(U104-NC-Pad5)") (class "Default")
      (node (ref "U104") (pin "5") (pinfunction "NC_5") (pintype "passive+no_connect"))
    )
    (net (code "41") (name "unconnected-(U105-NC-Pad5)") (class "Default")
      (node (ref "U105") (pin "5") (pinfunction "NC_5") (pintype "passive+no_connect"))
    )
    (net (code "42") (name "unconnected-(U107-N{slash}C-Pad4)") (class "Default")
      (node (ref "U107") (pin "4") (pinfunction "N/C_4") (pintype "passive+no_connect"))
    )
    (net (code "43") (name "unconnected-(U108-N{slash}C-Pad4)") (class "Default")
      (node (ref "U108") (pin "4") (pinfunction "N/C_4") (pintype "passive+no_connect"))
    )
    (net (code "44") (name "unconnected-(U109-N{slash}C-Pad4)") (class "Default")
      (node (ref "U109") (pin "4") (pinfunction "N/C_4") (pintype "passive+no_connect"))
    )
  )
)
